# binary_clock_rev2.net
KiCad netlist of a schematic drawn in EAGLE
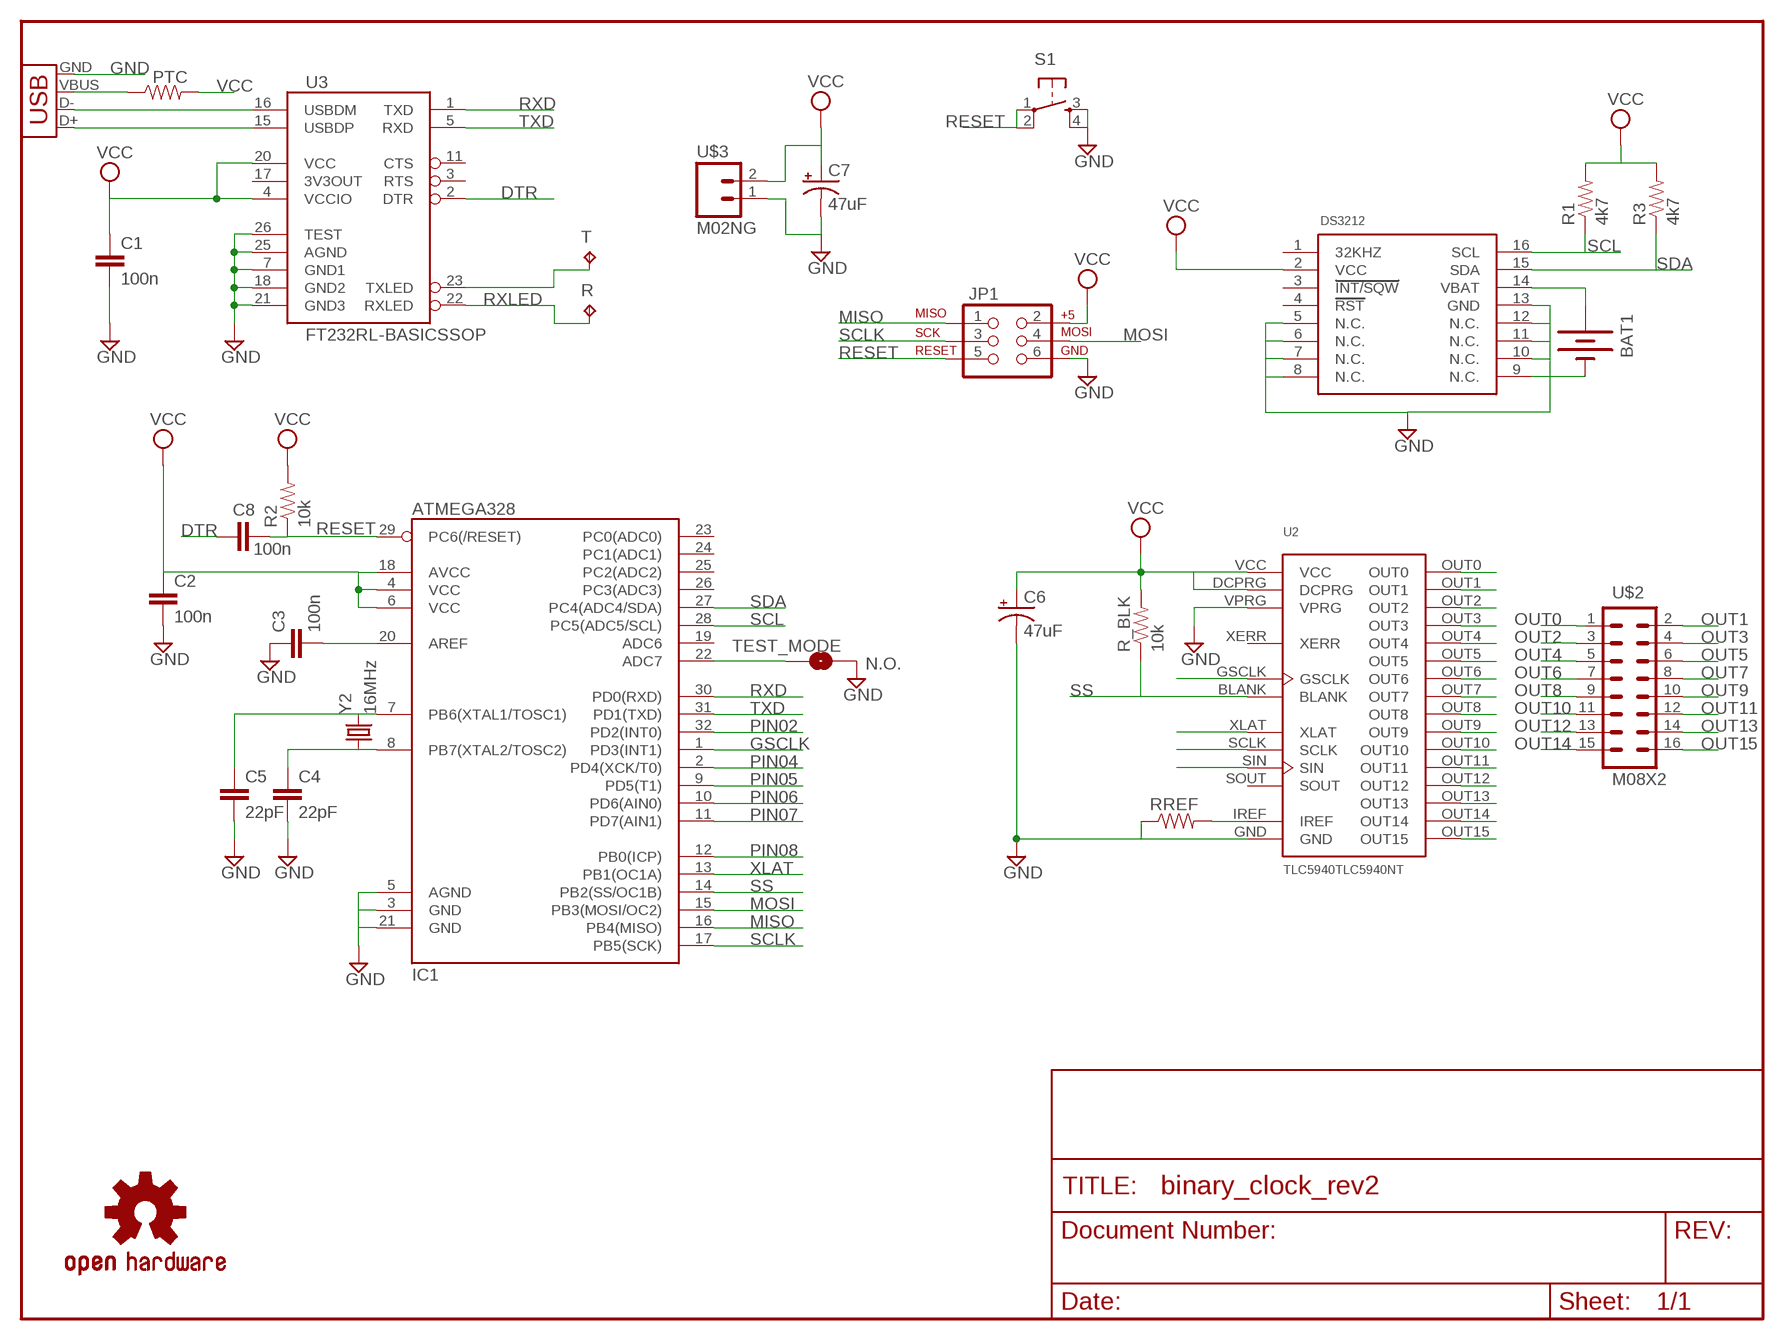
[diagram p0: schematic, sheet 1]

(export (version "E")
  (design (tool "Eeschema 10.0.6"))
  (components
    (comp (ref "BAT1")
      (value "BATTERY12MM")
      (footprint "eagle-import:BATTCON_12MM")
      (libsource (lib "eagle-import") (part "BATTERY12MM"))
    )
    (comp (ref "C1")
      (value "100n")
      (footprint "eagle-import:1206")
      (libsource (lib "eagle-import") (part "SparkFun_CAP1206"))
    )
    (comp (ref "C2")
      (value "100n")
      (footprint "eagle-import:1206")
      (libsource (lib "eagle-import") (part "SparkFun_CAP1206"))
    )
    (comp (ref "C3")
      (value "100n")
      (footprint "eagle-import:1206")
      (libsource (lib "eagle-import") (part "SparkFun_CAP1206"))
    )
    (comp (ref "C4")
      (value "22pF")
      (footprint "eagle-import:1206")
      (libsource (lib "eagle-import") (part "CAP1206"))
    )
    (comp (ref "C5")
      (value "22pF")
      (footprint "eagle-import:1206")
      (libsource (lib "eagle-import") (part "CAP1206"))
    )
    (comp (ref "C6")
      (value "47uF")
      (footprint "eagle-import:D_7343-31W")
      (libsource (lib "eagle-import") (part "CPOL-USD/7343-31W"))
    )
    (comp (ref "C7")
      (value "47uF")
      (footprint "eagle-import:D_7343-31W")
      (libsource (lib "eagle-import") (part "CPOL-USD/7343-31W"))
    )
    (comp (ref "C8")
      (value "100n")
      (footprint "eagle-import:1206")
      (libsource (lib "eagle-import") (part "SparkFun_CAP1206"))
    )
    (comp (ref "DS3212")
      (value "DS3231")
      (footprint "eagle-import:SO16L")
      (libsource (lib "eagle-import") (part "DS3231"))
    )
    (comp (ref "IC1")
      (value "ATMEGA328")
      (footprint "eagle-import:TQFP32-08")
      (libsource (lib "eagle-import") (part "ATMEGA168"))
    )
    (comp (ref "JP1")
      (value "AVR_SPI_PRG_62X3_LOCK")
      (footprint "eagle-import:2X3_LOCK")
      (libsource (lib "eagle-import") (part "AVR_SPI_PRG_62X3_LOCK"))
    )
    (comp (ref "PTC")
      (value "RESISTOR1206")
      (footprint "eagle-import:1206")
      (libsource (lib "eagle-import") (part "SparkFun_RESISTOR1206"))
    )
    (comp (ref "R")
      (value "TPB1,27")
      (footprint "eagle-import:B1,27")
      (libsource (lib "eagle-import") (part "TPB1,27"))
    )
    (comp (ref "R1")
      (value "4k7")
      (footprint "eagle-import:1206")
      (libsource (lib "eagle-import") (part "SparkFun_RESISTOR1206"))
    )
    (comp (ref "R2")
      (value "10k")
      (footprint "eagle-import:1206")
      (libsource (lib "eagle-import") (part "SparkFun_RESISTOR1206"))
    )
    (comp (ref "R3")
      (value "4k7")
      (footprint "eagle-import:1206")
      (libsource (lib "eagle-import") (part "SparkFun_RESISTOR1206"))
    )
    (comp (ref "RREF")
      (value "2.2k")
      (footprint "eagle-import:1206")
      (libsource (lib "eagle-import") (part "RESISTOR1206"))
    )
    (comp (ref "R_BLK")
      (value "10k")
      (footprint "eagle-import:1206")
      (libsource (lib "eagle-import") (part "RESISTOR1206"))
    )
    (comp (ref "S1")
      (value "TAC_SWITCHSMD")
      (footprint "eagle-import:TACTILE_SWITCH_SMD")
      (libsource (lib "eagle-import") (part "TAC_SWITCHSMD"))
    )
    (comp (ref "T")
      (value "TPB1,27")
      (footprint "eagle-import:B1,27")
      (libsource (lib "eagle-import") (part "TPB1,27"))
    )
    (comp (ref "TEST_MODE")
      (value "N.O.")
      (footprint "eagle-import:SJ_2S-NO")
      (libsource (lib "eagle-import") (part "SOLDERJUMPERNO"))
    )
    (comp (ref "U$1")
      (value "OSHW-LOGOM")
      (footprint "eagle-import:OSHW-LOGO-M")
      (libsource (lib "eagle-import") (part "OSHW-LOGOM"))
    )
    (comp (ref "U$2")
      (value "M08X2")
      (footprint "eagle-import:2X8")
      (libsource (lib "eagle-import") (part "M08X2"))
    )
    (comp (ref "U$3")
      (value "M02NG")
      (footprint "eagle-import:1X02")
      (libsource (lib "eagle-import") (part "M02NG"))
    )
    (comp (ref "U2")
      (value "TLC5940TLC5940NT")
      (footprint "eagle-import:DIL28-3")
      (libsource (lib "eagle-import") (part "TLC5940TLC5940NT"))
    )
    (comp (ref "U3")
      (value "FT232RL-BASICSSOP")
      (footprint "eagle-import:SSOP28DB")
      (libsource (lib "eagle-import") (part "FT232RL-BASICSSOP"))
    )
    (comp (ref "X1")
      (value "USBSMD")
      (footprint "eagle-import:USB-MINIB")
      (libsource (lib "eagle-import") (part "USBSMD"))
    )
    (comp (ref "Y2")
      (value "16MHz")
      (footprint "eagle-import:HC49US")
      (libsource (lib "eagle-import") (part "CRYSTALHC49US"))
    )
  )
  (nets
    (net (code "1") (name "/DTR") (class "Default")
      (node (ref "C8") (pin "1") (pinfunction "1_1") (pintype "passive"))
      (node (ref "U3") (pin "2") (pinfunction "DTR_2") (pintype "bidirectional"))
    )
    (net (code "2") (name "/GSCLK") (class "Default")
      (node (ref "IC1") (pin "1") (pinfunction "PD3(INT1)_1") (pintype "bidirectional"))
      (node (ref "U2") (pin "GSCLK") (pinfunction "GSCLK_GSCLK") (pintype "input"))
    )
    (net (code "3") (name "/MISO") (class "Default")
      (node (ref "IC1") (pin "16") (pinfunction "PB4(MISO)_16") (pintype "bidirectional"))
      (node (ref "JP1") (pin "1") (pinfunction "1_1") (pintype "passive"))
    )
    (net (code "4") (name "/MOSI") (class "Default")
      (node (ref "IC1") (pin "15") (pinfunction "PB3(MOSI/OC2)_15") (pintype "bidirectional"))
      (node (ref "JP1") (pin "4") (pinfunction "4_4") (pintype "passive"))
      (node (ref "U2") (pin "SIN") (pinfunction "SIN_SIN") (pintype "input"))
    )
    (net (code "5") (name "/OUT0") (class "Default")
      (node (ref "U$2") (pin "1") (pinfunction "1_1") (pintype "passive"))
      (node (ref "U2") (pin "OUT0") (pinfunction "OUT0_OUT0") (pintype "output"))
    )
    (net (code "6") (name "/OUT1") (class "Default")
      (node (ref "U$2") (pin "2") (pinfunction "2_2") (pintype "passive"))
      (node (ref "U2") (pin "OUT1") (pinfunction "OUT1_OUT1") (pintype "output"))
    )
    (net (code "7") (name "/OUT2") (class "Default")
      (node (ref "U$2") (pin "3") (pinfunction "3_3") (pintype "passive"))
      (node (ref "U2") (pin "OUT2") (pinfunction "OUT2_OUT2") (pintype "output"))
    )
    (net (code "8") (name "/OUT3") (class "Default")
      (node (ref "U$2") (pin "4") (pinfunction "4_4") (pintype "passive"))
      (node (ref "U2") (pin "OUT3") (pinfunction "OUT3_OUT3") (pintype "output"))
    )
    (net (code "9") (name "/OUT4") (class "Default")
      (node (ref "U$2") (pin "5") (pinfunction "5_5") (pintype "passive"))
      (node (ref "U2") (pin "OUT4") (pinfunction "OUT4_OUT4") (pintype "output"))
    )
    (net (code "10") (name "/OUT5") (class "Default")
      (node (ref "U$2") (pin "6") (pinfunction "6_6") (pintype "passive"))
      (node (ref "U2") (pin "OUT5") (pinfunction "OUT5_OUT5") (pintype "output"))
    )
    (net (code "11") (name "/OUT6") (class "Default")
      (node (ref "U$2") (pin "7") (pinfunction "7_7") (pintype "passive"))
      (node (ref "U2") (pin "OUT6") (pinfunction "OUT6_OUT6") (pintype "output"))
    )
    (net (code "12") (name "/OUT7") (class "Default")
      (node (ref "U$2") (pin "8") (pinfunction "8_8") (pintype "passive"))
      (node (ref "U2") (pin "OUT7") (pinfunction "OUT7_OUT7") (pintype "output"))
    )
    (net (code "13") (name "/OUT8") (class "Default")
      (node (ref "U$2") (pin "9") (pinfunction "9_9") (pintype "passive"))
      (node (ref "U2") (pin "OUT8") (pinfunction "OUT8_OUT8") (pintype "output"))
    )
    (net (code "14") (name "/OUT9") (class "Default")
      (node (ref "U$2") (pin "10") (pinfunction "10_10") (pintype "passive"))
      (node (ref "U2") (pin "OUT9") (pinfunction "OUT9_OUT9") (pintype "output"))
    )
    (net (code "15") (name "/OUT10") (class "Default")
      (node (ref "U$2") (pin "11") (pinfunction "11_11") (pintype "passive"))
      (node (ref "U2") (pin "OUT10") (pinfunction "OUT10_OUT10") (pintype "output"))
    )
    (net (code "16") (name "/OUT11") (class "Default")
      (node (ref "U$2") (pin "12") (pinfunction "12_12") (pintype "passive"))
      (node (ref "U2") (pin "OUT11") (pinfunction "OUT11_OUT11") (pintype "output"))
    )
    (net (code "17") (name "/OUT12") (class "Default")
      (node (ref "U$2") (pin "13") (pinfunction "13_13") (pintype "passive"))
      (node (ref "U2") (pin "OUT12") (pinfunction "OUT12_OUT12") (pintype "output"))
    )
    (net (code "18") (name "/OUT13") (class "Default")
      (node (ref "U$2") (pin "14") (pinfunction "14_14") (pintype "passive"))
      (node (ref "U2") (pin "OUT13") (pinfunction "OUT13_OUT13") (pintype "output"))
    )
    (net (code "19") (name "/OUT14") (class "Default")
      (node (ref "U$2") (pin "15") (pinfunction "15_15") (pintype "passive"))
      (node (ref "U2") (pin "OUT14") (pinfunction "OUT14_OUT14") (pintype "output"))
    )
    (net (code "20") (name "/OUT15") (class "Default")
      (node (ref "U$2") (pin "16") (pinfunction "16_16") (pintype "passive"))
      (node (ref "U2") (pin "OUT15") (pinfunction "OUT15_OUT15") (pintype "output"))
    )
    (net (code "21") (name "/PIN02") (class "Default")
      (node (ref "IC1") (pin "32") (pinfunction "PD2(INT0)_32") (pintype "bidirectional"))
    )
    (net (code "22") (name "/PIN04") (class "Default")
      (node (ref "IC1") (pin "2") (pinfunction "PD4(XCK/T0)_2") (pintype "bidirectional"))
    )
    (net (code "23") (name "/PIN05") (class "Default")
      (node (ref "IC1") (pin "9") (pinfunction "PD5(T1)_9") (pintype "bidirectional"))
    )
    (net (code "24") (name "/PIN06") (class "Default")
      (node (ref "IC1") (pin "10") (pinfunction "PD6(AIN0)_10") (pintype "bidirectional"))
    )
    (net (code "25") (name "/PIN07") (class "Default")
      (node (ref "IC1") (pin "11") (pinfunction "PD7(AIN1)_11") (pintype "bidirectional"))
    )
    (net (code "26") (name "/PIN08") (class "Default")
      (node (ref "IC1") (pin "12") (pinfunction "PB0(ICP)_12") (pintype "bidirectional"))
    )
    (net (code "27") (name "/RESET") (class "Default")
      (node (ref "C8") (pin "2") (pinfunction "2_2") (pintype "passive"))
      (node (ref "IC1") (pin "29") (pinfunction "PC6(/RESET)_29") (pintype "bidirectional"))
      (node (ref "JP1") (pin "5") (pinfunction "5_5") (pintype "passive"))
      (node (ref "R2") (pin "1") (pinfunction "1_1") (pintype "passive"))
      (node (ref "S1") (pin "1") (pinfunction "1_1") (pintype "passive"))
      (node (ref "S1") (pin "2") (pinfunction "2_2") (pintype "passive"))
    )
    (net (code "28") (name "/RXD") (class "Default")
      (node (ref "IC1") (pin "30") (pinfunction "PD0(RXD)_30") (pintype "bidirectional"))
      (node (ref "U3") (pin "1") (pinfunction "TXD_1") (pintype "output"))
    )
    (net (code "29") (name "/RXLED") (class "Default")
      (node (ref "R") (pin "TP") (pinfunction "TP_TP") (pintype "input"))
      (node (ref "U3") (pin "22") (pinfunction "RXLED_22") (pintype "bidirectional"))
    )
    (net (code "30") (name "/SCL") (class "Default")
      (node (ref "DS3212") (pin "16") (pinfunction "SCL_16") (pintype "bidirectional"))
      (node (ref "IC1") (pin "28") (pinfunction "PC5(ADC5/SCL)_28") (pintype "bidirectional"))
      (node (ref "R1") (pin "1") (pinfunction "1_1") (pintype "passive"))
    )
    (net (code "31") (name "/SCLK") (class "Default")
      (node (ref "IC1") (pin "17") (pinfunction "PB5(SCK)_17") (pintype "bidirectional"))
      (node (ref "JP1") (pin "3") (pinfunction "3_3") (pintype "passive"))
      (node (ref "U2") (pin "SCLK") (pinfunction "SCLK_SCLK") (pintype "input"))
    )
    (net (code "32") (name "/SDA") (class "Default")
      (node (ref "DS3212") (pin "15") (pinfunction "SDA_15") (pintype "bidirectional"))
      (node (ref "IC1") (pin "27") (pinfunction "PC4(ADC4/SDA)_27") (pintype "bidirectional"))
      (node (ref "R3") (pin "1") (pinfunction "1_1") (pintype "passive"))
    )
    (net (code "33") (name "/SS") (class "Default")
      (node (ref "IC1") (pin "14") (pinfunction "PB2(SS/OC1B)_14") (pintype "bidirectional"))
      (node (ref "R_BLK") (pin "1") (pinfunction "1_1") (pintype "passive"))
      (node (ref "U2") (pin "BLANK") (pinfunction "BLANK_BLANK") (pintype "bidirectional"))
    )
    (net (code "34") (name "/TXD") (class "Default")
      (node (ref "IC1") (pin "31") (pinfunction "PD1(TXD)_31") (pintype "bidirectional"))
      (node (ref "U3") (pin "5") (pinfunction "RXD_5") (pintype "input"))
    )
    (net (code "35") (name "/XLAT") (class "Default")
      (node (ref "IC1") (pin "13") (pinfunction "PB1(OC1A)_13") (pintype "bidirectional"))
      (node (ref "U2") (pin "XLAT") (pinfunction "XLAT_XLAT") (pintype "input"))
    )
    (net (code "36") (name "GND") (class "Default")
      (node (ref "BAT1") (pin "GND") (pinfunction "-_GND") (pintype "power_in"))
      (node (ref "C1") (pin "2") (pinfunction "2_2") (pintype "passive"))
      (node (ref "C2") (pin "2") (pinfunction "2_2") (pintype "passive"))
      (node (ref "C3") (pin "1") (pinfunction "1_1") (pintype "passive"))
      (node (ref "C4") (pin "2") (pinfunction "2_2") (pintype "passive"))
      (node (ref "C5") (pin "2") (pinfunction "2_2") (pintype "passive"))
      (node (ref "C6") (pin "-") (pinfunction "-_-") (pintype "passive"))
      (node (ref "C7") (pin "-") (pinfunction "-_-") (pintype "passive"))
      (node (ref "DS3212") (pin "10") (pinfunction "N.C._10") (pintype "bidirectional"))
      (node (ref "DS3212") (pin "11") (pinfunction "N.C._11") (pintype "bidirectional"))
      (node (ref "DS3212") (pin "12") (pinfunction "N.C._12") (pintype "bidirectional"))
      (node (ref "DS3212") (pin "13") (pinfunction "GND_13") (pintype "power_in"))
      (node (ref "DS3212") (pin "5") (pinfunction "N.C._5") (pintype "bidirectional"))
      (node (ref "DS3212") (pin "6") (pinfunction "N.C._6") (pintype "bidirectional"))
      (node (ref "DS3212") (pin "7") (pinfunction "N.C._7") (pintype "bidirectional"))
      (node (ref "DS3212") (pin "8") (pinfunction "N.C._8") (pintype "bidirectional"))
      (node (ref "DS3212") (pin "9") (pinfunction "N.C._9") (pintype "bidirectional"))
      (node (ref "IC1") (pin "21") (pinfunction "GND_21") (pintype "bidirectional"))
      (node (ref "IC1") (pin "3") (pinfunction "GND_3") (pintype "bidirectional"))
      (node (ref "IC1") (pin "5") (pinfunction "AGND_5") (pintype "bidirectional"))
      (node (ref "JP1") (pin "6") (pinfunction "6_6") (pintype "passive"))
      (node (ref "RREF") (pin "1") (pinfunction "1_1") (pintype "passive"))
      (node (ref "S1") (pin "3") (pinfunction "3_3") (pintype "passive"))
      (node (ref "S1") (pin "4") (pinfunction "4_4") (pintype "passive"))
      (node (ref "TEST_MODE") (pin "2") (pinfunction "2_2") (pintype "passive"))
      (node (ref "U$3") (pin "1") (pinfunction "1_1") (pintype "passive"))
      (node (ref "U2") (pin "GND") (pinfunction "GND_GND") (pintype "power_in"))
      (node (ref "U2") (pin "VPRG") (pinfunction "VPRG_VPRG") (pintype "input"))
      (node (ref "U3") (pin "18") (pinfunction "GND2_18") (pintype "power_in"))
      (node (ref "U3") (pin "21") (pinfunction "GND3_21") (pintype "power_in"))
      (node (ref "U3") (pin "25") (pinfunction "AGND_25") (pintype "power_in"))
      (node (ref "U3") (pin "26") (pinfunction "TEST_26") (pintype "input"))
      (node (ref "U3") (pin "7") (pinfunction "GND1_7") (pintype "power_in"))
      (node (ref "X1") (pin "GND") (pinfunction "GND_GND") (pintype "bidirectional"))
    )
    (net (code "37") (name "Net-(BAT1-+)") (class "Default")
      (node (ref "BAT1") (pin "PWR@2") (pinfunction "+_PWR@2") (pintype "power_in"))
      (node (ref "DS3212") (pin "14") (pinfunction "VBAT_14") (pintype "power_in"))
    )
    (net (code "38") (name "Net-(IC1-ADC7)") (class "Default")
      (node (ref "IC1") (pin "22") (pinfunction "ADC7_22") (pintype "bidirectional"))
      (node (ref "TEST_MODE") (pin "1") (pinfunction "1_1") (pintype "passive"))
    )
    (net (code "39") (name "Net-(IC1-AREF)") (class "Default")
      (node (ref "C3") (pin "2") (pinfunction "2_2") (pintype "passive"))
      (node (ref "IC1") (pin "20") (pinfunction "AREF_20") (pintype "bidirectional"))
    )
    (net (code "40") (name "Net-(IC1-PB6(XTAL1{slash}TOSC1))") (class "Default")
      (node (ref "C5") (pin "1") (pinfunction "1_1") (pintype "passive"))
      (node (ref "IC1") (pin "7") (pinfunction "PB6(XTAL1/TOSC1)_7") (pintype "bidirectional"))
      (node (ref "Y2") (pin "2") (pinfunction "2_2") (pintype "passive"))
    )
    (net (code "41") (name "Net-(IC1-PB7(XTAL2{slash}TOSC2))") (class "Default")
      (node (ref "C4") (pin "1") (pinfunction "1_1") (pintype "passive"))
      (node (ref "IC1") (pin "8") (pinfunction "PB7(XTAL2/TOSC2)_8") (pintype "bidirectional"))
      (node (ref "Y2") (pin "1") (pinfunction "1_1") (pintype "passive"))
    )
    (net (code "42") (name "Net-(PTC-Pad1)") (class "Default")
      (node (ref "PTC") (pin "1") (pinfunction "1_1") (pintype "passive"))
      (node (ref "X1") (pin "VBUS") (pinfunction "VBUS_VBUS") (pintype "bidirectional"))
    )
    (net (code "43") (name "Net-(RREF-Pad2)") (class "Default")
      (node (ref "RREF") (pin "2") (pinfunction "2_2") (pintype "passive"))
      (node (ref "U2") (pin "IREF") (pinfunction "IREF_IREF") (pintype "input"))
    )
    (net (code "44") (name "Net-(U3-TXLED)") (class "Default")
      (node (ref "T") (pin "TP") (pinfunction "TP_TP") (pintype "input"))
      (node (ref "U3") (pin "23") (pinfunction "TXLED_23") (pintype "bidirectional"))
    )
    (net (code "45") (name "Net-(U3-USBDM)") (class "Default")
      (node (ref "U3") (pin "16") (pinfunction "USBDM_16") (pintype "bidirectional"))
      (node (ref "X1") (pin "D-") (pinfunction "D-_D-") (pintype "bidirectional"))
    )
    (net (code "46") (name "Net-(U3-USBDP)") (class "Default")
      (node (ref "U3") (pin "15") (pinfunction "USBDP_15") (pintype "bidirectional"))
      (node (ref "X1") (pin "D+") (pinfunction "D+_D+") (pintype "bidirectional"))
    )
    (net (code "47") (name "VCC") (class "Default")
      (node (ref "C1") (pin "1") (pinfunction "1_1") (pintype "passive"))
      (node (ref "C2") (pin "1") (pinfunction "1_1") (pintype "passive"))
      (node (ref "C6") (pin "+") (pinfunction "+_+") (pintype "passive"))
      (node (ref "C7") (pin "+") (pinfunction "+_+") (pintype "passive"))
      (node (ref "DS3212") (pin "2") (pinfunction "VCC_2") (pintype "power_in"))
      (node (ref "IC1") (pin "18") (pinfunction "AVCC_18") (pintype "bidirectional"))
      (node (ref "IC1") (pin "4") (pinfunction "VCC_4") (pintype "bidirectional"))
      (node (ref "IC1") (pin "6") (pinfunction "VCC_6") (pintype "bidirectional"))
      (node (ref "JP1") (pin "2") (pinfunction "2_2") (pintype "passive"))
      (node (ref "PTC") (pin "2") (pinfunction "2_2") (pintype "passive"))
      (node (ref "R1") (pin "2") (pinfunction "2_2") (pintype "passive"))
      (node (ref "R2") (pin "2") (pinfunction "2_2") (pintype "passive"))
      (node (ref "R3") (pin "2") (pinfunction "2_2") (pintype "passive"))
      (node (ref "R_BLK") (pin "2") (pinfunction "2_2") (pintype "passive"))
      (node (ref "U$3") (pin "2") (pinfunction "2_2") (pintype "passive"))
      (node (ref "U2") (pin "DCPRG") (pinfunction "DCPRG_DCPRG") (pintype "input"))
      (node (ref "U2") (pin "VCC") (pinfunction "VCC_VCC") (pintype "power_in"))
      (node (ref "U3") (pin "20") (pinfunction "VCC_20") (pintype "power_in"))
      (node (ref "U3") (pin "4") (pinfunction "VCCIO_4") (pintype "power_in"))
    )
    (net (code "48") (name "unconnected-(DS3212-32KHZ-Pad1)") (class "Default")
      (node (ref "DS3212") (pin "1") (pinfunction "32KHZ_1") (pintype "bidirectional"))
    )
    (net (code "49") (name "unconnected-(DS3212-INT{slash}SQW-Pad3)") (class "Default")
      (node (ref "DS3212") (pin "3") (pinfunction "INT/SQW_3") (pintype "bidirectional"))
    )
    (net (code "50") (name "unconnected-(DS3212-RST-Pad4)") (class "Default")
      (node (ref "DS3212") (pin "4") (pinfunction "RST_4") (pintype "bidirectional"))
    )
    (net (code "51") (name "unconnected-(IC1-ADC6-Pad19)") (class "Default")
      (node (ref "IC1") (pin "19") (pinfunction "ADC6_19") (pintype "bidirectional"))
    )
    (net (code "52") (name "unconnected-(IC1-PC0(ADC0)-Pad23)") (class "Default")
      (node (ref "IC1") (pin "23") (pinfunction "PC0(ADC0)_23") (pintype "bidirectional"))
    )
    (net (code "53") (name "unconnected-(IC1-PC1(ADC1)-Pad24)") (class "Default")
      (node (ref "IC1") (pin "24") (pinfunction "PC1(ADC1)_24") (pintype "bidirectional"))
    )
    (net (code "54") (name "unconnected-(IC1-PC2(ADC2)-Pad25)") (class "Default")
      (node (ref "IC1") (pin "25") (pinfunction "PC2(ADC2)_25") (pintype "bidirectional"))
    )
    (net (code "55") (name "unconnected-(IC1-PC3(ADC3)-Pad26)") (class "Default")
      (node (ref "IC1") (pin "26") (pinfunction "PC3(ADC3)_26") (pintype "bidirectional"))
    )
    (net (code "56") (name "unconnected-(U2-PadSOUT)") (class "Default")
      (node (ref "U2") (pin "SOUT") (pinfunction "SOUT_SOUT") (pintype "output"))
    )
    (net (code "57") (name "unconnected-(U2-PadXERR)") (class "Default")
      (node (ref "U2") (pin "XERR") (pinfunction "XERR_XERR") (pintype "output"))
    )
    (net (code "58") (name "unconnected-(U3-3V3OUT-Pad17)") (class "Default")
      (node (ref "U3") (pin "17") (pinfunction "3V3OUT_17") (pintype "output"))
    )
    (net (code "59") (name "unconnected-(U3-CTS-Pad11)") (class "Default")
      (node (ref "U3") (pin "11") (pinfunction "CTS_11") (pintype "bidirectional"))
    )
    (net (code "60") (name "unconnected-(U3-RTS-Pad3)") (class "Default")
      (node (ref "U3") (pin "3") (pinfunction "RTS_3") (pintype "bidirectional"))
    )
  )
)
